# MYC_Homematic.net
KiCad netlist of a schematic drawn in EAGLE
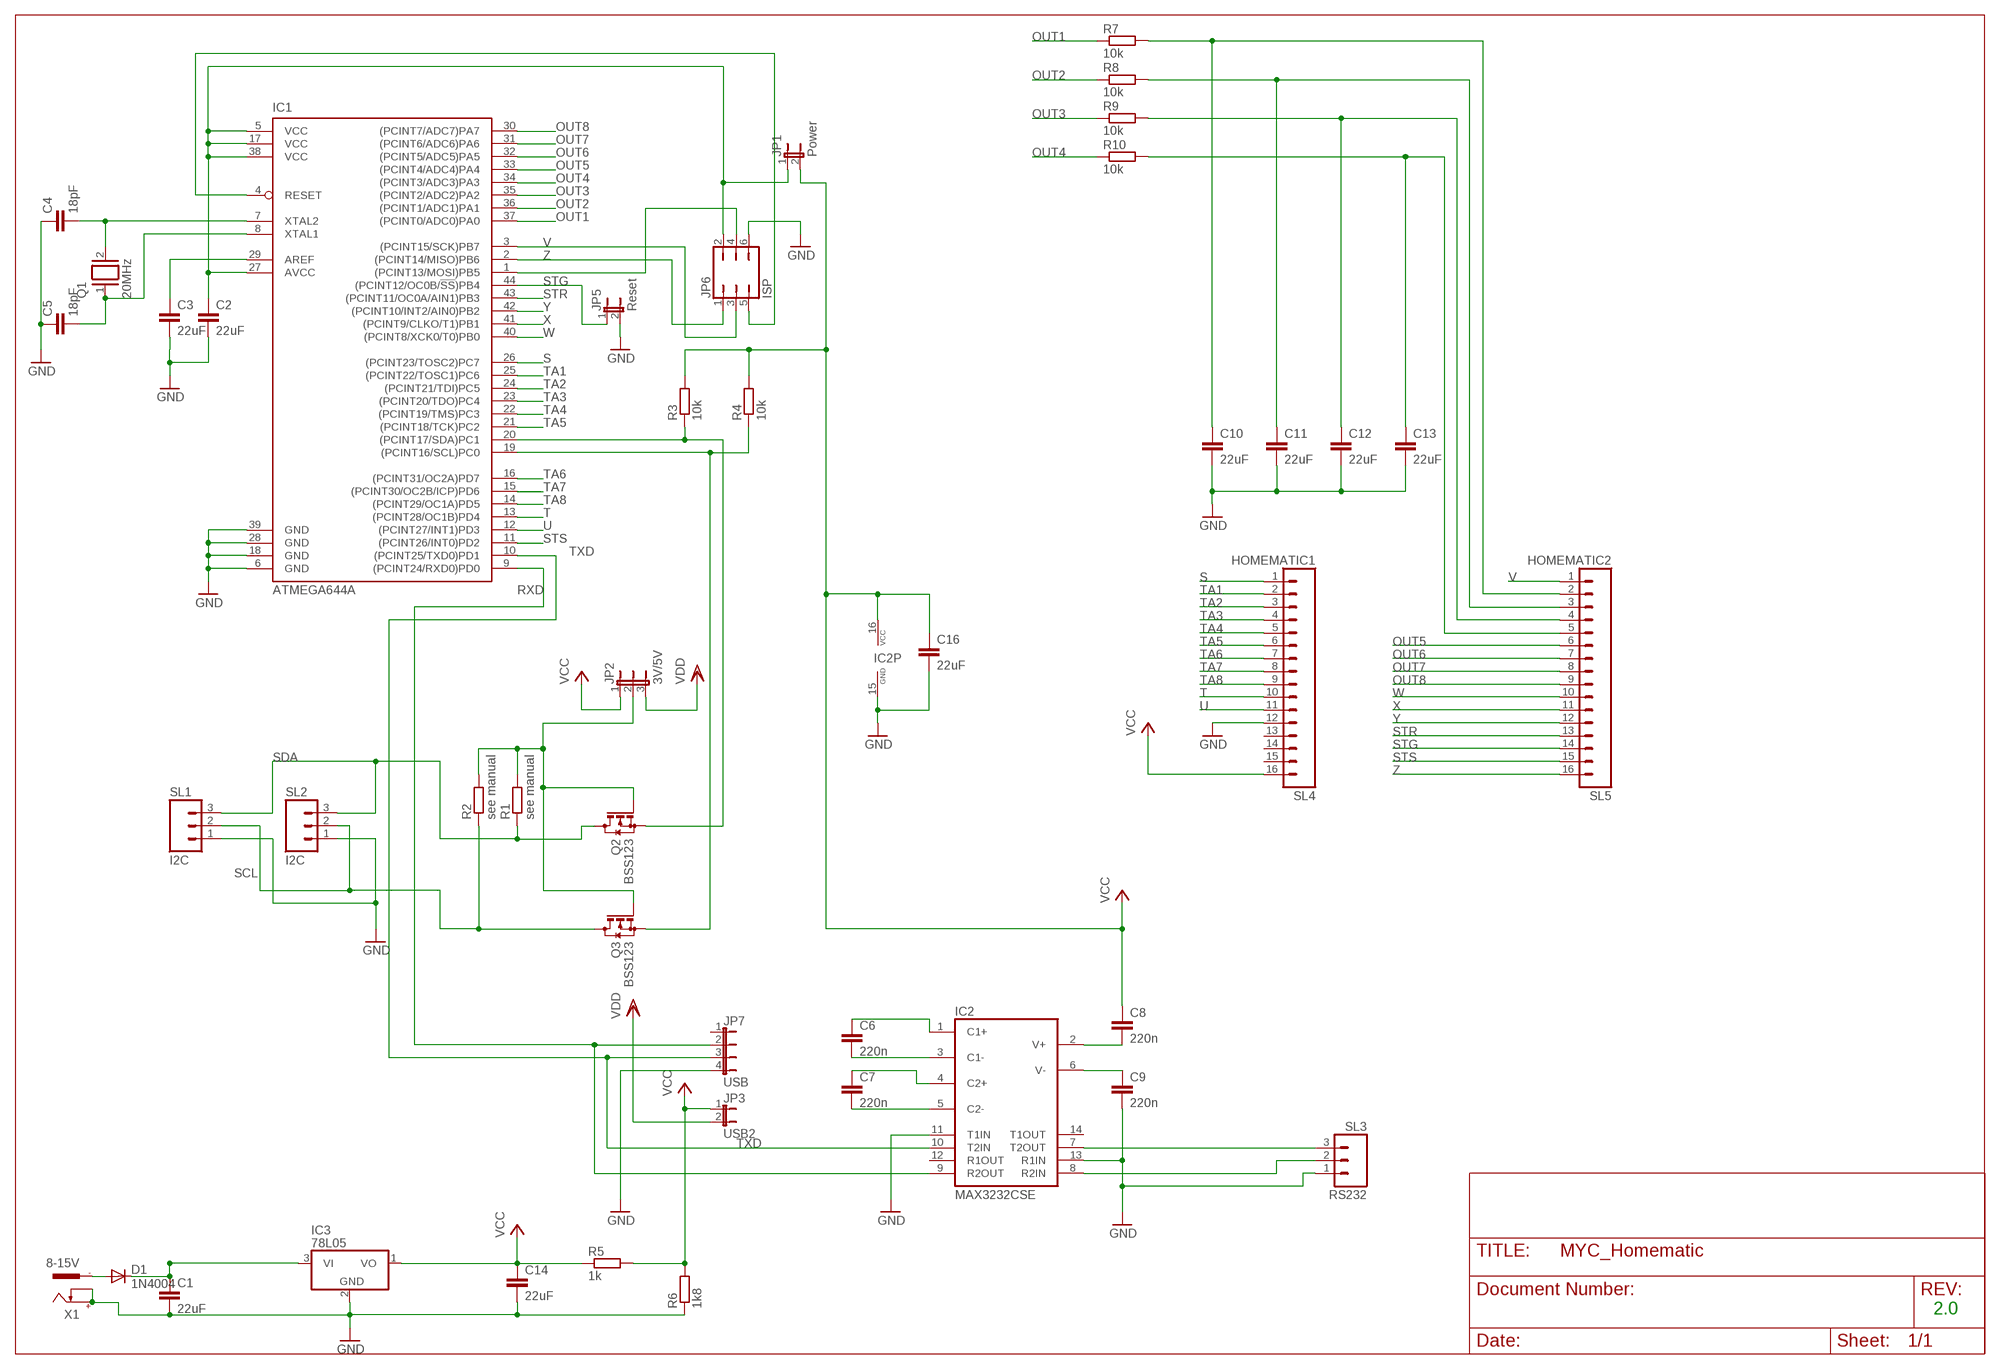
[diagram p0: schematic, sheet 1]

(export (version "E")
  (design (tool "Eeschema 10.0.6"))
  (components
    (comp (ref "C1")
      (value "22uF")
      (footprint "eagle-import:C1206")
      (libsource (lib "eagle-import") (part "C-EUC1206"))
    )
    (comp (ref "C2")
      (value "22uF")
      (footprint "eagle-import:C1206")
      (libsource (lib "eagle-import") (part "C-EUC1206"))
    )
    (comp (ref "C3")
      (value "22uF")
      (footprint "eagle-import:C1206")
      (libsource (lib "eagle-import") (part "C-EUC1206"))
    )
    (comp (ref "C4")
      (value "18pF")
      (footprint "eagle-import:C025-030X050")
      (libsource (lib "eagle-import") (part "C-EU025-030X050"))
    )
    (comp (ref "C5")
      (value "18pF")
      (footprint "eagle-import:C025-030X050")
      (libsource (lib "eagle-import") (part "C-EU025-030X050"))
    )
    (comp (ref "C6")
      (value "220n")
      (footprint "eagle-import:C1206")
      (libsource (lib "eagle-import") (part "C-EUC1206"))
    )
    (comp (ref "C7")
      (value "220n")
      (footprint "eagle-import:C1206")
      (libsource (lib "eagle-import") (part "C-EUC1206"))
    )
    (comp (ref "C8")
      (value "220n")
      (footprint "eagle-import:C1206")
      (libsource (lib "eagle-import") (part "C-EUC1206"))
    )
    (comp (ref "C9")
      (value "220n")
      (footprint "eagle-import:C1206")
      (libsource (lib "eagle-import") (part "C-EUC1206"))
    )
    (comp (ref "C10")
      (value "22uF")
      (footprint "eagle-import:C1206")
      (libsource (lib "eagle-import") (part "C-EUC1206"))
    )
    (comp (ref "C11")
      (value "22uF")
      (footprint "eagle-import:C1206")
      (libsource (lib "eagle-import") (part "C-EUC1206"))
    )
    (comp (ref "C12")
      (value "22uF")
      (footprint "eagle-import:C1206")
      (libsource (lib "eagle-import") (part "C-EUC1206"))
    )
    (comp (ref "C13")
      (value "22uF")
      (footprint "eagle-import:C1206")
      (libsource (lib "eagle-import") (part "C-EUC1206"))
    )
    (comp (ref "C14")
      (value "22uF")
      (footprint "eagle-import:C1206")
      (libsource (lib "eagle-import") (part "C-EUC1206"))
    )
    (comp (ref "C16")
      (value "22uF")
      (footprint "eagle-import:C1206")
      (libsource (lib "eagle-import") (part "C-EUC1206"))
    )
    (comp (ref "D1")
      (value "1N4004")
      (footprint "eagle-import:DO41-10")
      (libsource (lib "eagle-import") (part "1N4004"))
    )
    (comp (ref "IC1")
      (value "ATMEGA644A")
      (footprint "eagle-import:TQFP44")
      (fields (field (name "MPN") "ATMEGA644PV-10AU"))
      (libsource (lib "eagle-import") (part "ATMEGA644A"))
    )
    (comp (ref "IC2")
      (value "MAX3232CSE")
      (footprint "eagle-import:SO16")
      (libsource (lib "eagle-import") (part "MAX3232SEC"))
    )
    (comp (ref "IC3")
      (value "78L05")
      (footprint "eagle-import:TO92")
      (libsource (lib "eagle-import") (part "78L05"))
    )
    (comp (ref "JP1")
      (value "Power")
      (footprint "eagle-import:JP1")
      (libsource (lib "eagle-import") (part "JP1E"))
    )
    (comp (ref "JP2")
      (value "3V/5V")
      (footprint "eagle-import:JP2")
      (libsource (lib "eagle-import") (part "JP2E"))
    )
    (comp (ref "JP3")
      (value "USB2")
      (footprint "eagle-import:JP1")
      (libsource (lib "eagle-import") (part "JP1E"))
    )
    (comp (ref "JP5")
      (value "Reset")
      (footprint "eagle-import:JP1")
      (libsource (lib "eagle-import") (part "JP1E"))
    )
    (comp (ref "JP6")
      (value "ISP")
      (footprint "eagle-import:JP3Q")
      (libsource (lib "eagle-import") (part "JP3Q"))
    )
    (comp (ref "JP7")
      (value "USB")
      (footprint "eagle-import:JP4")
      (libsource (lib "eagle-import") (part "JP4E"))
    )
    (comp (ref "Q1")
      (value "20MHz")
      (footprint "eagle-import:QS")
      (libsource (lib "eagle-import") (part "XTAL/S"))
    )
    (comp (ref "Q2")
      (value "BSS123")
      (footprint "eagle-import:SOT23")
      (libsource (lib "eagle-import") (part "BSS123"))
    )
    (comp (ref "Q3")
      (value "BSS123")
      (footprint "eagle-import:SOT23")
      (libsource (lib "eagle-import") (part "BSS123"))
    )
    (comp (ref "R1")
      (value "see manual")
      (footprint "eagle-import:R1206")
      (libsource (lib "eagle-import") (part "R-EU_R1206"))
    )
    (comp (ref "R2")
      (value "see manual")
      (footprint "eagle-import:R1206")
      (libsource (lib "eagle-import") (part "R-EU_R1206"))
    )
    (comp (ref "R3")
      (value "10k")
      (footprint "eagle-import:R1206")
      (libsource (lib "eagle-import") (part "R-EU_R1206"))
    )
    (comp (ref "R4")
      (value "10k")
      (footprint "eagle-import:R1206")
      (libsource (lib "eagle-import") (part "R-EU_R1206"))
    )
    (comp (ref "R5")
      (value "1k")
      (footprint "eagle-import:R1206")
      (libsource (lib "eagle-import") (part "R-EU_R1206"))
    )
    (comp (ref "R6")
      (value "1k8")
      (footprint "eagle-import:R1206")
      (libsource (lib "eagle-import") (part "R-EU_R1206"))
    )
    (comp (ref "R7")
      (value "10k")
      (footprint "eagle-import:R1206")
      (libsource (lib "eagle-import") (part "R-EU_R1206"))
    )
    (comp (ref "R8")
      (value "10k")
      (footprint "eagle-import:R1206")
      (libsource (lib "eagle-import") (part "R-EU_R1206"))
    )
    (comp (ref "R9")
      (value "10k")
      (footprint "eagle-import:R1206")
      (libsource (lib "eagle-import") (part "R-EU_R1206"))
    )
    (comp (ref "R10")
      (value "10k")
      (footprint "eagle-import:R1206")
      (libsource (lib "eagle-import") (part "R-EU_R1206"))
    )
    (comp (ref "SL1")
      (value "I2C")
      (footprint "eagle-import:03P")
      (libsource (lib "eagle-import") (part "M03"))
    )
    (comp (ref "SL2")
      (value "I2C")
      (footprint "eagle-import:03P")
      (libsource (lib "eagle-import") (part "M03"))
    )
    (comp (ref "SL3")
      (value "RS232")
      (footprint "eagle-import:03P")
      (libsource (lib "eagle-import") (part "M03"))
    )
    (comp (ref "SL4")
      (value "HOMEMATIC1")
      (footprint "eagle-import:16P")
      (libsource (lib "eagle-import") (part "M16"))
    )
    (comp (ref "SL5")
      (value "HOMEMATIC2")
      (footprint "eagle-import:16P")
      (libsource (lib "eagle-import") (part "M16"))
    )
    (comp (ref "X1")
      (value "8-15V")
      (footprint "eagle-import:737992-5")
      (libsource (lib "eagle-import") (part "737992-55"))
    )
  )
  (nets
    (net (code "1") (name "/OUT1") (class "Default")
      (node (ref "IC1") (pin "37") (pinfunction "(PCINT0/ADC0)PA0_37") (pintype "bidirectional"))
      (node (ref "R7") (pin "1") (pinfunction "1_1") (pintype "passive"))
    )
    (net (code "2") (name "/OUT2") (class "Default")
      (node (ref "IC1") (pin "36") (pinfunction "(PCINT1/ADC1)PA1_36") (pintype "bidirectional"))
      (node (ref "R8") (pin "1") (pinfunction "1_1") (pintype "passive"))
    )
    (net (code "3") (name "/OUT3") (class "Default")
      (node (ref "IC1") (pin "35") (pinfunction "(PCINT2/ADC2)PA2_35") (pintype "bidirectional"))
      (node (ref "R9") (pin "1") (pinfunction "1_1") (pintype "passive"))
    )
    (net (code "4") (name "/OUT4") (class "Default")
      (node (ref "IC1") (pin "34") (pinfunction "(PCINT3/ADC3)PA3_34") (pintype "bidirectional"))
      (node (ref "R10") (pin "1") (pinfunction "1_1") (pintype "passive"))
    )
    (net (code "5") (name "/OUT5") (class "Default")
      (node (ref "IC1") (pin "33") (pinfunction "(PCINT4/ADC4)PA4_33") (pintype "bidirectional"))
      (node (ref "SL5") (pin "6") (pinfunction "6_6") (pintype "passive"))
    )
    (net (code "6") (name "/OUT6") (class "Default")
      (node (ref "IC1") (pin "32") (pinfunction "(PCINT5/ADC5)PA5_32") (pintype "bidirectional"))
      (node (ref "SL5") (pin "7") (pinfunction "7_7") (pintype "passive"))
    )
    (net (code "7") (name "/OUT7") (class "Default")
      (node (ref "IC1") (pin "31") (pinfunction "(PCINT6/ADC6)PA6_31") (pintype "bidirectional"))
      (node (ref "SL5") (pin "8") (pinfunction "8_8") (pintype "passive"))
    )
    (net (code "8") (name "/OUT8") (class "Default")
      (node (ref "IC1") (pin "30") (pinfunction "(PCINT7/ADC7)PA7_30") (pintype "bidirectional"))
      (node (ref "SL5") (pin "9") (pinfunction "9_9") (pintype "passive"))
    )
    (net (code "9") (name "/RXD") (class "Default")
      (node (ref "IC1") (pin "9") (pinfunction "(PCINT24/RXD0)PD0_9") (pintype "bidirectional"))
      (node (ref "IC2") (pin "9") (pinfunction "R2OUT_9") (pintype "output"))
      (node (ref "JP7") (pin "2") (pinfunction "2_2") (pintype "passive"))
    )
    (net (code "10") (name "/S") (class "Default")
      (node (ref "IC1") (pin "26") (pinfunction "(PCINT23/TOSC2)PC7_26") (pintype "output"))
      (node (ref "SL4") (pin "1") (pinfunction "1_1") (pintype "passive"))
    )
    (net (code "11") (name "/SCL") (class "Default")
      (node (ref "Q3") (pin "3") (pinfunction "D_3") (pintype "passive"))
      (node (ref "R2") (pin "1") (pinfunction "1_1") (pintype "passive"))
      (node (ref "SL1") (pin "2") (pinfunction "2_2") (pintype "passive"))
      (node (ref "SL2") (pin "2") (pinfunction "2_2") (pintype "passive"))
    )
    (net (code "12") (name "/SDA") (class "Default")
      (node (ref "Q2") (pin "3") (pinfunction "D_3") (pintype "passive"))
      (node (ref "R1") (pin "1") (pinfunction "1_1") (pintype "passive"))
      (node (ref "SL1") (pin "3") (pinfunction "3_3") (pintype "passive"))
      (node (ref "SL2") (pin "3") (pinfunction "3_3") (pintype "passive"))
    )
    (net (code "13") (name "/STG") (class "Default")
      (node (ref "IC1") (pin "44") (pinfunction "(PCINT12/OC0B/~{SS})PB4_44") (pintype "bidirectional"))
      (node (ref "JP5") (pin "1") (pinfunction "1_1") (pintype "passive"))
      (node (ref "SL5") (pin "14") (pinfunction "14_14") (pintype "passive"))
    )
    (net (code "14") (name "/STR") (class "Default")
      (node (ref "IC1") (pin "43") (pinfunction "(PCINT11/OC0A/AIN1)PB3_43") (pintype "bidirectional"))
      (node (ref "SL5") (pin "13") (pinfunction "13_13") (pintype "passive"))
    )
    (net (code "15") (name "/STS") (class "Default")
      (node (ref "IC1") (pin "11") (pinfunction "(PCINT26/INT0)PD2_11") (pintype "bidirectional"))
      (node (ref "SL5") (pin "15") (pinfunction "15_15") (pintype "passive"))
    )
    (net (code "16") (name "/T") (class "Default")
      (node (ref "IC1") (pin "13") (pinfunction "(PCINT28/OC1B)PD4_13") (pintype "bidirectional"))
      (node (ref "SL4") (pin "10") (pinfunction "10_10") (pintype "passive"))
    )
    (net (code "17") (name "/TA1") (class "Default")
      (node (ref "IC1") (pin "25") (pinfunction "(PCINT22/TOSC1)PC6_25") (pintype "output"))
      (node (ref "SL4") (pin "2") (pinfunction "2_2") (pintype "passive"))
    )
    (net (code "18") (name "/TA2") (class "Default")
      (node (ref "IC1") (pin "24") (pinfunction "(PCINT21/TDI)PC5_24") (pintype "output"))
      (node (ref "SL4") (pin "3") (pinfunction "3_3") (pintype "passive"))
    )
    (net (code "19") (name "/TA3") (class "Default")
      (node (ref "IC1") (pin "23") (pinfunction "(PCINT20/TDO)PC4_23") (pintype "output"))
      (node (ref "SL4") (pin "4") (pinfunction "4_4") (pintype "passive"))
    )
    (net (code "20") (name "/TA4") (class "Default")
      (node (ref "IC1") (pin "22") (pinfunction "(PCINT19/TMS)PC3_22") (pintype "output"))
      (node (ref "SL4") (pin "5") (pinfunction "5_5") (pintype "passive"))
    )
    (net (code "21") (name "/TA5") (class "Default")
      (node (ref "IC1") (pin "21") (pinfunction "(PCINT18/TCK)PC2_21") (pintype "output"))
      (node (ref "SL4") (pin "6") (pinfunction "6_6") (pintype "passive"))
    )
    (net (code "22") (name "/TA6") (class "Default")
      (node (ref "IC1") (pin "16") (pinfunction "(PCINT31/OC2A)PD7_16") (pintype "bidirectional"))
      (node (ref "SL4") (pin "7") (pinfunction "7_7") (pintype "passive"))
    )
    (net (code "23") (name "/TA7") (class "Default")
      (node (ref "IC1") (pin "15") (pinfunction "(PCINT30/OC2B/ICP)PD6_15") (pintype "bidirectional"))
      (node (ref "SL4") (pin "8") (pinfunction "8_8") (pintype "passive"))
    )
    (net (code "24") (name "/TA8") (class "Default")
      (node (ref "IC1") (pin "14") (pinfunction "(PCINT29/OC1A)PD5_14") (pintype "bidirectional"))
      (node (ref "SL4") (pin "9") (pinfunction "9_9") (pintype "passive"))
    )
    (net (code "25") (name "/TXD") (class "Default")
      (node (ref "IC1") (pin "10") (pinfunction "(PCINT25/TXD0)PD1_10") (pintype "bidirectional"))
      (node (ref "IC2") (pin "10") (pinfunction "T2IN_10") (pintype "input"))
      (node (ref "JP7") (pin "3") (pinfunction "3_3") (pintype "passive"))
    )
    (net (code "26") (name "/U") (class "Default")
      (node (ref "IC1") (pin "12") (pinfunction "(PCINT27/INT1)PD3_12") (pintype "bidirectional"))
      (node (ref "SL4") (pin "11") (pinfunction "11_11") (pintype "passive"))
    )
    (net (code "27") (name "/V") (class "Default")
      (node (ref "IC1") (pin "3") (pinfunction "(PCINT15/SCK)PB7_3") (pintype "bidirectional"))
      (node (ref "JP6") (pin "3") (pinfunction "3_3") (pintype "passive"))
      (node (ref "SL5") (pin "1") (pinfunction "1_1") (pintype "passive"))
    )
    (net (code "28") (name "/W") (class "Default")
      (node (ref "IC1") (pin "40") (pinfunction "(PCINT8/XCK0/T0)PB0_40") (pintype "bidirectional"))
      (node (ref "SL5") (pin "10") (pinfunction "10_10") (pintype "passive"))
    )
    (net (code "29") (name "/X") (class "Default")
      (node (ref "IC1") (pin "41") (pinfunction "(PCINT9/CLKO/T1)PB1_41") (pintype "bidirectional"))
      (node (ref "SL5") (pin "11") (pinfunction "11_11") (pintype "passive"))
    )
    (net (code "30") (name "/Y") (class "Default")
      (node (ref "IC1") (pin "42") (pinfunction "(PCINT10/INT2/AIN0)PB2_42") (pintype "bidirectional"))
      (node (ref "SL5") (pin "12") (pinfunction "12_12") (pintype "passive"))
    )
    (net (code "31") (name "/Z") (class "Default")
      (node (ref "IC1") (pin "2") (pinfunction "(PCINT14/MISO)PB6_2") (pintype "bidirectional"))
      (node (ref "JP6") (pin "1") (pinfunction "1_1") (pintype "passive"))
      (node (ref "SL5") (pin "16") (pinfunction "16_16") (pintype "passive"))
    )
    (net (code "32") (name "GND") (class "Default")
      (node (ref "C1") (pin "2") (pinfunction "2_2") (pintype "passive"))
      (node (ref "C10") (pin "2") (pinfunction "2_2") (pintype "passive"))
      (node (ref "C11") (pin "2") (pinfunction "2_2") (pintype "passive"))
      (node (ref "C12") (pin "2") (pinfunction "2_2") (pintype "passive"))
      (node (ref "C13") (pin "2") (pinfunction "2_2") (pintype "passive"))
      (node (ref "C14") (pin "2") (pinfunction "2_2") (pintype "passive"))
      (node (ref "C16") (pin "2") (pinfunction "2_2") (pintype "passive"))
      (node (ref "C2") (pin "2") (pinfunction "2_2") (pintype "passive"))
      (node (ref "C3") (pin "2") (pinfunction "2_2") (pintype "passive"))
      (node (ref "C4") (pin "1") (pinfunction "1_1") (pintype "passive"))
      (node (ref "C5") (pin "1") (pinfunction "1_1") (pintype "passive"))
      (node (ref "C9") (pin "2") (pinfunction "2_2") (pintype "passive"))
      (node (ref "IC1") (pin "18") (pinfunction "GND_18") (pintype "power_in"))
      (node (ref "IC1") (pin "28") (pinfunction "GND_28") (pintype "power_in"))
      (node (ref "IC1") (pin "39") (pinfunction "GND_39") (pintype "power_in"))
      (node (ref "IC1") (pin "6") (pinfunction "GND_6") (pintype "power_in"))
      (node (ref "IC2") (pin "11") (pinfunction "T1IN_11") (pintype "input"))
      (node (ref "IC2") (pin "13") (pinfunction "R1IN_13") (pintype "input"))
      (node (ref "IC2") (pin "15") (pinfunction "GND_15") (pintype "power_in"))
      (node (ref "IC3") (pin "2") (pinfunction "GND_2") (pintype "passive"))
      (node (ref "JP5") (pin "2") (pinfunction "2_2") (pintype "passive"))
      (node (ref "JP6") (pin "6") (pinfunction "6_6") (pintype "passive"))
      (node (ref "JP7") (pin "4") (pinfunction "4_4") (pintype "passive"))
      (node (ref "R6") (pin "1") (pinfunction "1_1") (pintype "passive"))
      (node (ref "SL1") (pin "1") (pinfunction "1_1") (pintype "passive"))
      (node (ref "SL2") (pin "1") (pinfunction "1_1") (pintype "passive"))
      (node (ref "SL3") (pin "1") (pinfunction "1_1") (pintype "passive"))
      (node (ref "SL4") (pin "12") (pinfunction "12_12") (pintype "passive"))
      (node (ref "X1") (pin "+") (pinfunction "+_+") (pintype "passive"))
      (node (ref "X1") (pin "K") (pinfunction "K_K") (pintype "passive"))
    )
    (net (code "33") (name "Net-(C10-Pad1)") (class "Default")
      (node (ref "C10") (pin "1") (pinfunction "1_1") (pintype "passive"))
      (node (ref "R7") (pin "2") (pinfunction "2_2") (pintype "passive"))
      (node (ref "SL5") (pin "2") (pinfunction "2_2") (pintype "passive"))
    )
    (net (code "34") (name "Net-(C11-Pad1)") (class "Default")
      (node (ref "C11") (pin "1") (pinfunction "1_1") (pintype "passive"))
      (node (ref "R8") (pin "2") (pinfunction "2_2") (pintype "passive"))
      (node (ref "SL5") (pin "3") (pinfunction "3_3") (pintype "passive"))
    )
    (net (code "35") (name "Net-(C12-Pad1)") (class "Default")
      (node (ref "C12") (pin "1") (pinfunction "1_1") (pintype "passive"))
      (node (ref "R9") (pin "2") (pinfunction "2_2") (pintype "passive"))
      (node (ref "SL5") (pin "4") (pinfunction "4_4") (pintype "passive"))
    )
    (net (code "36") (name "Net-(C13-Pad1)") (class "Default")
      (node (ref "C13") (pin "1") (pinfunction "1_1") (pintype "passive"))
      (node (ref "R10") (pin "2") (pinfunction "2_2") (pintype "passive"))
      (node (ref "SL5") (pin "5") (pinfunction "5_5") (pintype "passive"))
    )
    (net (code "37") (name "Net-(D1-PadA)") (class "Default")
      (node (ref "D1") (pin "A") (pinfunction "A_A") (pintype "passive"))
      (node (ref "X1") (pin "-1") (pinfunction "-1_-1") (pintype "passive"))
    )
    (net (code "38") (name "Net-(IC1-(PCINT13{slash}MOSI)PB5)") (class "Default")
      (node (ref "IC1") (pin "1") (pinfunction "(PCINT13/MOSI)PB5_1") (pintype "bidirectional"))
      (node (ref "JP6") (pin "4") (pinfunction "4_4") (pintype "passive"))
    )
    (net (code "39") (name "Net-(IC1-(PCINT16{slash}SCL)PC0)") (class "Default")
      (node (ref "IC1") (pin "19") (pinfunction "(PCINT16/SCL)PC0_19") (pintype "output"))
      (node (ref "Q3") (pin "2") (pinfunction "S_2") (pintype "passive"))
      (node (ref "R4") (pin "1") (pinfunction "1_1") (pintype "passive"))
    )
    (net (code "40") (name "Net-(IC1-(PCINT17{slash}SDA)PC1)") (class "Default")
      (node (ref "IC1") (pin "20") (pinfunction "(PCINT17/SDA)PC1_20") (pintype "output"))
      (node (ref "Q2") (pin "2") (pinfunction "S_2") (pintype "passive"))
      (node (ref "R3") (pin "1") (pinfunction "1_1") (pintype "passive"))
    )
    (net (code "41") (name "Net-(IC1-AREF)") (class "Default")
      (node (ref "C3") (pin "1") (pinfunction "1_1") (pintype "passive"))
      (node (ref "IC1") (pin "29") (pinfunction "AREF_29") (pintype "passive"))
    )
    (net (code "42") (name "Net-(IC1-AVCC)") (class "Default")
      (node (ref "C2") (pin "1") (pinfunction "1_1") (pintype "passive"))
      (node (ref "IC1") (pin "17") (pinfunction "VCC_17") (pintype "power_in"))
      (node (ref "IC1") (pin "27") (pinfunction "AVCC_27") (pintype "power_in"))
      (node (ref "IC1") (pin "38") (pinfunction "VCC_38") (pintype "power_in"))
      (node (ref "IC1") (pin "5") (pinfunction "VCC_5") (pintype "power_in"))
      (node (ref "JP1") (pin "1") (pinfunction "1_1") (pintype "passive"))
      (node (ref "JP6") (pin "2") (pinfunction "2_2") (pintype "passive"))
    )
    (net (code "43") (name "Net-(IC1-RESET)") (class "Default")
      (node (ref "IC1") (pin "4") (pinfunction "RESET_4") (pintype "input"))
      (node (ref "JP6") (pin "5") (pinfunction "5_5") (pintype "passive"))
    )
    (net (code "44") (name "Net-(IC1-XTAL1)") (class "Default")
      (node (ref "C5") (pin "2") (pinfunction "2_2") (pintype "passive"))
      (node (ref "IC1") (pin "8") (pinfunction "XTAL1_8") (pintype "bidirectional"))
      (node (ref "Q1") (pin "1") (pinfunction "1_1") (pintype "passive"))
    )
    (net (code "45") (name "Net-(IC1-XTAL2)") (class "Default")
      (node (ref "C4") (pin "2") (pinfunction "2_2") (pintype "passive"))
      (node (ref "IC1") (pin "7") (pinfunction "XTAL2_7") (pintype "bidirectional"))
      (node (ref "Q1") (pin "2") (pinfunction "2_2") (pintype "passive"))
    )
    (net (code "46") (name "Net-(IC2A-C1+)") (class "Default")
      (node (ref "C6") (pin "1") (pinfunction "1_1") (pintype "passive"))
      (node (ref "IC2") (pin "1") (pinfunction "C1+_1") (pintype "bidirectional"))
    )
    (net (code "47") (name "Net-(IC2A-C1-)") (class "Default")
      (node (ref "C6") (pin "2") (pinfunction "2_2") (pintype "passive"))
      (node (ref "IC2") (pin "3") (pinfunction "C1-_3") (pintype "bidirectional"))
    )
    (net (code "48") (name "Net-(IC2A-C2+)") (class "Default")
      (node (ref "C7") (pin "1") (pinfunction "1_1") (pintype "passive"))
      (node (ref "IC2") (pin "4") (pinfunction "C2+_4") (pintype "bidirectional"))
    )
    (net (code "49") (name "Net-(IC2A-C2-)") (class "Default")
      (node (ref "C7") (pin "2") (pinfunction "2_2") (pintype "passive"))
      (node (ref "IC2") (pin "5") (pinfunction "C2-_5") (pintype "bidirectional"))
    )
    (net (code "50") (name "Net-(IC2A-R2IN)") (class "Default")
      (node (ref "IC2") (pin "8") (pinfunction "R2IN_8") (pintype "input"))
      (node (ref "SL3") (pin "2") (pinfunction "2_2") (pintype "passive"))
    )
    (net (code "51") (name "Net-(IC2A-T2OUT)") (class "Default")
      (node (ref "IC2") (pin "7") (pinfunction "T2OUT_7") (pintype "output"))
      (node (ref "SL3") (pin "3") (pinfunction "3_3") (pintype "passive"))
    )
    (net (code "52") (name "Net-(IC2A-V+)") (class "Default")
      (node (ref "C8") (pin "2") (pinfunction "2_2") (pintype "passive"))
      (node (ref "IC2") (pin "2") (pinfunction "V+_2") (pintype "bidirectional"))
    )
    (net (code "53") (name "Net-(IC2A-V-)") (class "Default")
      (node (ref "C9") (pin "1") (pinfunction "1_1") (pintype "passive"))
      (node (ref "IC2") (pin "6") (pinfunction "V-_6") (pintype "bidirectional"))
    )
    (net (code "54") (name "Net-(IC3-VI)") (class "Default")
      (node (ref "C1") (pin "1") (pinfunction "1_1") (pintype "passive"))
      (node (ref "D1") (pin "C") (pinfunction "C_C") (pintype "passive"))
      (node (ref "IC3") (pin "3") (pinfunction "VI_3") (pintype "input"))
    )
    (net (code "55") (name "Net-(Q2-G)") (class "Default")
      (node (ref "JP2") (pin "2") (pinfunction "2_2") (pintype "passive"))
      (node (ref "Q2") (pin "1") (pinfunction "G_1") (pintype "passive"))
      (node (ref "Q3") (pin "1") (pinfunction "G_1") (pintype "passive"))
      (node (ref "R1") (pin "2") (pinfunction "2_2") (pintype "passive"))
      (node (ref "R2") (pin "2") (pinfunction "2_2") (pintype "passive"))
    )
    (net (code "56") (name "VCC") (class "Default")
      (node (ref "C14") (pin "1") (pinfunction "1_1") (pintype "passive"))
      (node (ref "C16") (pin "1") (pinfunction "1_1") (pintype "passive"))
      (node (ref "C8") (pin "1") (pinfunction "1_1") (pintype "passive"))
      (node (ref "IC2") (pin "16") (pinfunction "VCC_16") (pintype "power_in"))
      (node (ref "IC3") (pin "1") (pinfunction "VO_1") (pintype "passive"))
      (node (ref "JP1") (pin "2") (pinfunction "2_2") (pintype "passive"))
      (node (ref "JP2") (pin "1") (pinfunction "1_1") (pintype "passive"))
      (node (ref "JP3") (pin "1") (pinfunction "1_1") (pintype "passive"))
      (node (ref "R3") (pin "2") (pinfunction "2_2") (pintype "passive"))
      (node (ref "R4") (pin "2") (pinfunction "2_2") (pintype "passive"))
      (node (ref "R5") (pin "1") (pinfunction "1_1") (pintype "passive"))
      (node (ref "R5") (pin "2") (pinfunction "2_2") (pintype "passive"))
      (node (ref "R6") (pin "2") (pinfunction "2_2") (pintype "passive"))
      (node (ref "SL4") (pin "16") (pinfunction "16_16") (pintype "passive"))
    )
    (net (code "57") (name "VDD") (class "Default")
      (node (ref "JP2") (pin "3") (pinfunction "3_3") (pintype "passive"))
      (node (ref "JP3") (pin "2") (pinfunction "2_2") (pintype "passive"))
    )
    (net (code "58") (name "unconnected-(IC2A-R1OUT-Pad12)") (class "Default")
      (node (ref "IC2") (pin "12") (pinfunction "R1OUT_12") (pintype "output"))
    )
    (net (code "59") (name "unconnected-(IC2A-T1OUT-Pad14)") (class "Default")
      (node (ref "IC2") (pin "14") (pinfunction "T1OUT_14") (pintype "output"))
    )
    (net (code "60") (name "unconnected-(JP7-Pad1)") (class "Default")
      (node (ref "JP7") (pin "1") (pinfunction "1_1") (pintype "passive"))
    )
    (net (code "61") (name "unconnected-(SL4-Pad13)") (class "Default")
      (node (ref "SL4") (pin "13") (pinfunction "13_13") (pintype "passive"))
    )
    (net (code "62") (name "unconnected-(SL4-Pad14)") (class "Default")
      (node (ref "SL4") (pin "14") (pinfunction "14_14") (pintype "passive"))
    )
    (net (code "63") (name "unconnected-(SL4-Pad15)") (class "Default")
      (node (ref "SL4") (pin "15") (pinfunction "15_15") (pintype "passive"))
    )
    (net (code "64") (name "unconnected-(X1-Pad-2)") (class "Default")
      (node (ref "X1") (pin "-2") (pinfunction "-2_-2") (pintype "passive"))
    )
  )
)
